# Main-PCB.net
KiCad netlist of a schematic drawn in EAGLE
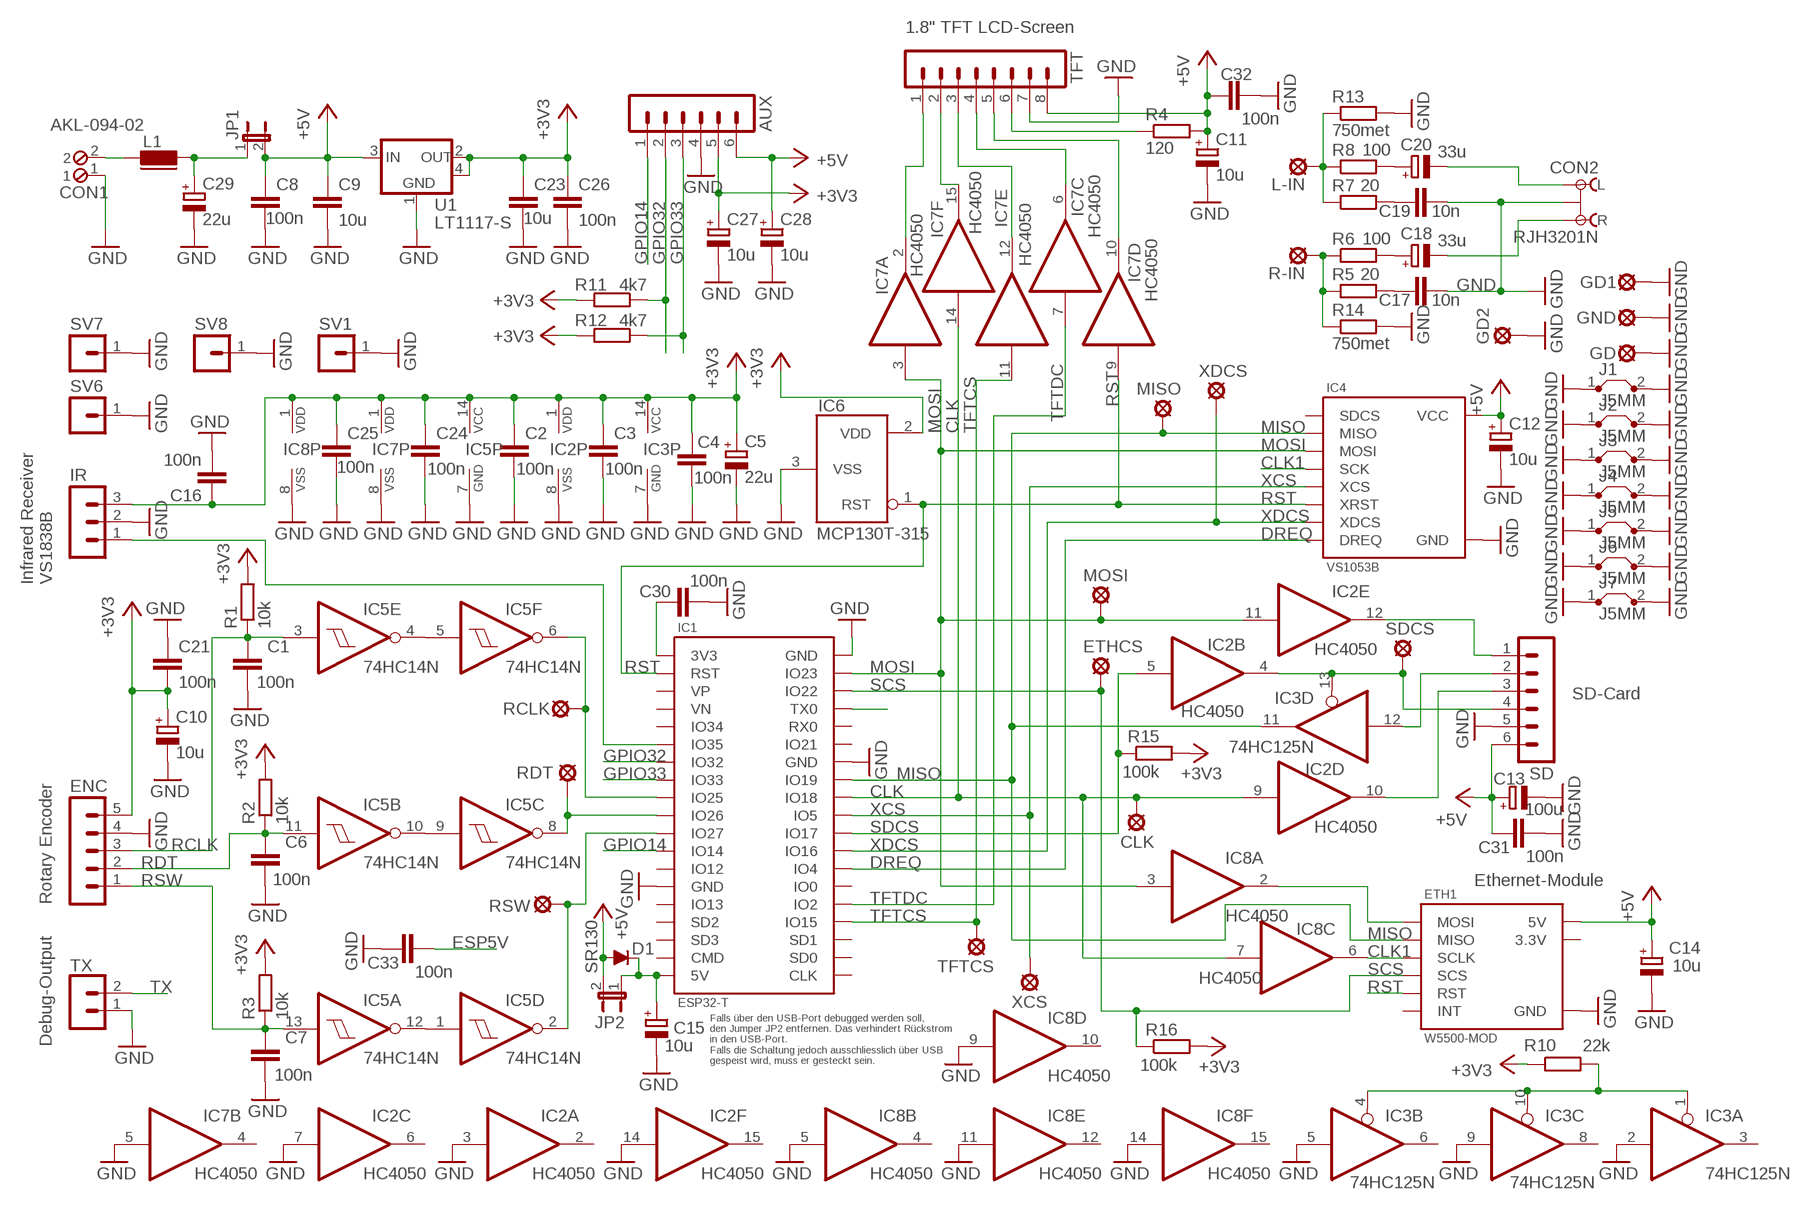
[diagram p0: schematic, sheet 1]

(export (version "E")
  (design (tool "Eeschema 10.0.6"))
  (components
    (comp (ref "AUX")
      (value "MA06-1")
      (footprint "eagle-import:MA06-1")
      (libsource (lib "eagle-import") (part "MA06-1"))
    )
    (comp (ref "C1")
      (value "100n")
      (footprint "eagle-import:C050-024X044")
      (libsource (lib "eagle-import") (part "C-EU050-024X044"))
    )
    (comp (ref "C2")
      (value "100n")
      (footprint "eagle-import:C1206")
      (libsource (lib "eagle-import") (part "C-EUC1206"))
    )
    (comp (ref "C3")
      (value "100n")
      (footprint "eagle-import:C1206")
      (libsource (lib "eagle-import") (part "C-EUC1206"))
    )
    (comp (ref "C4")
      (value "100n")
      (footprint "eagle-import:C1206")
      (libsource (lib "eagle-import") (part "C-EUC1206"))
    )
    (comp (ref "C5")
      (value "22u")
      (footprint "eagle-import:TT2D4")
      (libsource (lib "eagle-import") (part "CPOL-EUTT2D4"))
    )
    (comp (ref "C6")
      (value "100n")
      (footprint "eagle-import:C050-024X044")
      (libsource (lib "eagle-import") (part "C-EU050-024X044"))
    )
    (comp (ref "C7")
      (value "100n")
      (footprint "eagle-import:C050-024X044")
      (libsource (lib "eagle-import") (part "C-EU050-024X044"))
    )
    (comp (ref "C8")
      (value "100n")
      (footprint "eagle-import:C1206")
      (libsource (lib "eagle-import") (part "C-EUC1206"))
    )
    (comp (ref "C9")
      (value "10u")
      (footprint "eagle-import:C1206")
      (libsource (lib "eagle-import") (part "C-EUC1206"))
    )
    (comp (ref "C10")
      (value "10u")
      (footprint "eagle-import:TT2D4")
      (libsource (lib "eagle-import") (part "CPOL-EUTT2D4"))
    )
    (comp (ref "C11")
      (value "10u")
      (footprint "eagle-import:TT2D4")
      (libsource (lib "eagle-import") (part "CPOL-EUTT2D4"))
    )
    (comp (ref "C12")
      (value "10u")
      (footprint "eagle-import:TT2D4L")
      (libsource (lib "eagle-import") (part "CPOL-EUTT2D4L"))
    )
    (comp (ref "C13")
      (value "100u")
      (footprint "eagle-import:E2,5-6")
      (libsource (lib "eagle-import") (part "CPOL-EUE2.5-6"))
    )
    (comp (ref "C14")
      (value "10u")
      (footprint "eagle-import:TT2D4")
      (libsource (lib "eagle-import") (part "CPOL-EUTT2D4"))
    )
    (comp (ref "C15")
      (value "10u")
      (footprint "eagle-import:TT2D4")
      (libsource (lib "eagle-import") (part "CPOL-EUTT2D4"))
    )
    (comp (ref "C16")
      (value "100n")
      (footprint "eagle-import:C1206")
      (libsource (lib "eagle-import") (part "C-EUC1206"))
    )
    (comp (ref "C17")
      (value "10n")
      (footprint "eagle-import:C1206")
      (libsource (lib "eagle-import") (part "C-EUC1206"))
    )
    (comp (ref "C18")
      (value "33u")
      (footprint "eagle-import:TT2D4")
      (libsource (lib "eagle-import") (part "CPOL-EUTT2D4"))
    )
    (comp (ref "C19")
      (value "10n")
      (footprint "eagle-import:C1206")
      (libsource (lib "eagle-import") (part "C-EUC1206"))
    )
    (comp (ref "C20")
      (value "33u")
      (footprint "eagle-import:TT2D4")
      (libsource (lib "eagle-import") (part "CPOL-EUTT2D4"))
    )
    (comp (ref "C21")
      (value "100n")
      (footprint "eagle-import:C1206")
      (libsource (lib "eagle-import") (part "C-EUC1206"))
    )
    (comp (ref "C23")
      (value "10u")
      (footprint "eagle-import:C1206")
      (libsource (lib "eagle-import") (part "C-EUC1206"))
    )
    (comp (ref "C24")
      (value "100n")
      (footprint "eagle-import:C1206")
      (libsource (lib "eagle-import") (part "C-EUC1206"))
    )
    (comp (ref "C25")
      (value "100n")
      (footprint "eagle-import:C1206")
      (libsource (lib "eagle-import") (part "C-EUC1206"))
    )
    (comp (ref "C26")
      (value "100n")
      (footprint "eagle-import:C1206")
      (libsource (lib "eagle-import") (part "C-EUC1206"))
    )
    (comp (ref "C27")
      (value "10u")
      (footprint "eagle-import:TT2D4")
      (libsource (lib "eagle-import") (part "CPOL-EUTT2D4"))
    )
    (comp (ref "C28")
      (value "10u")
      (footprint "eagle-import:TT2D4")
      (libsource (lib "eagle-import") (part "CPOL-EUTT2D4"))
    )
    (comp (ref "C29")
      (value "22u")
      (footprint "eagle-import:TT2D4")
      (libsource (lib "eagle-import") (part "CPOL-EUTT2D4"))
    )
    (comp (ref "C30")
      (value "100n")
      (footprint "eagle-import:C1206")
      (libsource (lib "eagle-import") (part "C-EUC1206"))
    )
    (comp (ref "C31")
      (value "100n")
      (footprint "eagle-import:C1206")
      (libsource (lib "eagle-import") (part "C-EUC1206"))
    )
    (comp (ref "C32")
      (value "100n")
      (footprint "eagle-import:C1206")
      (libsource (lib "eagle-import") (part "C-EUC1206"))
    )
    (comp (ref "C33")
      (value "100n")
      (footprint "eagle-import:C1206")
      (libsource (lib "eagle-import") (part "C-EUC1206"))
    )
    (comp (ref "CLK")
      (value "LSP11")
      (footprint "eagle-import:LSP11")
      (libsource (lib "eagle-import") (part "LSP11"))
    )
    (comp (ref "CON1")
      (value "AKL-094-02")
      (footprint "eagle-import:AKL-094-02")
      (libsource (lib "eagle-import") (part "AKL-094-02"))
    )
    (comp (ref "CON2")
      (value "RJH3201N")
      (footprint "eagle-import:TECHNICS-RJH3201N")
      (libsource (lib "eagle-import") (part "RJH3201N"))
    )
    (comp (ref "D1")
      (value "SR130")
      (footprint "eagle-import:D-7.5")
      (libsource (lib "eagle-import") (part "DIODE-D-7.5"))
    )
    (comp (ref "ENC")
      (value "MA05-1")
      (footprint "eagle-import:MA05-1")
      (libsource (lib "eagle-import") (part "MA05-1"))
    )
    (comp (ref "ETH1")
      (value "W5500-MOD")
      (footprint "eagle-import:W5500-MOD")
      (libsource (lib "eagle-import") (part "W5500-MOD"))
    )
    (comp (ref "ETHCS")
      (value "LSP11")
      (footprint "eagle-import:LSP11")
      (libsource (lib "eagle-import") (part "LSP11"))
    )
    (comp (ref "GD")
      (value "LSP11")
      (footprint "eagle-import:LSP11")
      (libsource (lib "eagle-import") (part "LSP11"))
    )
    (comp (ref "GD1")
      (value "LSP11")
      (footprint "eagle-import:LSP11")
      (libsource (lib "eagle-import") (part "LSP11"))
    )
    (comp (ref "GD2")
      (value "SE13")
      (footprint "eagle-import:SE13")
      (libsource (lib "eagle-import") (part "SE13"))
    )
    (comp (ref "GND")
      (value "LSP11")
      (footprint "eagle-import:LSP11")
      (libsource (lib "eagle-import") (part "LSP11"))
    )
    (comp (ref "IC1")
      (value "ESP32-T")
      (footprint "eagle-import:ESP32-T")
      (libsource (lib "eagle-import") (part "ESP32-T"))
    )
    (comp (ref "IC2")
      (value "HC4050")
      (footprint "eagle-import:DIL16")
      (libsource (lib "eagle-import") (part "4050N"))
    )
    (comp (ref "IC3")
      (value "74HC125N")
      (footprint "eagle-import:DIL14")
      (libsource (lib "eagle-import") (part "74125NHC"))
    )
    (comp (ref "IC4")
      (value "VS1053B")
      (footprint "eagle-import:VS1053B")
      (libsource (lib "eagle-import") (part "VS1053B"))
    )
    (comp (ref "IC5")
      (value "74HC14N")
      (footprint "eagle-import:DIL14")
      (libsource (lib "eagle-import") (part "7414NHC"))
    )
    (comp (ref "IC6")
      (value "MCP130T-315")
      (footprint "eagle-import:SOT-23")
      (libsource (lib "eagle-import") (part "MCP130T-XXXSOT-23"))
    )
    (comp (ref "IC7")
      (value "HC4050")
      (footprint "eagle-import:DIL16")
      (libsource (lib "eagle-import") (part "4050N"))
    )
    (comp (ref "IC8")
      (value "HC4050")
      (footprint "eagle-import:DIL16")
      (libsource (lib "eagle-import") (part "4050N"))
    )
    (comp (ref "IR")
      (value "MA03-1")
      (footprint "eagle-import:MA03-1")
      (libsource (lib "eagle-import") (part "MA03-1"))
    )
    (comp (ref "J1")
      (value "J5MM")
      (footprint "eagle-import:05")
      (libsource (lib "eagle-import") (part "J5MM"))
    )
    (comp (ref "J2")
      (value "J5MM")
      (footprint "eagle-import:05")
      (libsource (lib "eagle-import") (part "J5MM"))
    )
    (comp (ref "J3")
      (value "J5MM")
      (footprint "eagle-import:05")
      (libsource (lib "eagle-import") (part "J5MM"))
    )
    (comp (ref "J4")
      (value "J5MM")
      (footprint "eagle-import:05")
      (libsource (lib "eagle-import") (part "J5MM"))
    )
    (comp (ref "J5")
      (value "J5MM")
      (footprint "eagle-import:05")
      (libsource (lib "eagle-import") (part "J5MM"))
    )
    (comp (ref "J6")
      (value "J5MM")
      (footprint "eagle-import:05")
      (libsource (lib "eagle-import") (part "J5MM"))
    )
    (comp (ref "J7")
      (value "J5MM")
      (footprint "eagle-import:05")
      (libsource (lib "eagle-import") (part "J5MM"))
    )
    (comp (ref "JP1")
      (value "JP1E")
      (footprint "eagle-import:JP1")
      (libsource (lib "eagle-import") (part "JP1E"))
    )
    (comp (ref "JP2")
      (value "JP1E")
      (footprint "eagle-import:JP1")
      (libsource (lib "eagle-import") (part "JP1E"))
    )
    (comp (ref "L-IN")
      (value "LSP11")
      (footprint "eagle-import:LSP11")
      (libsource (lib "eagle-import") (part "LSP11"))
    )
    (comp (ref "L1")
      (value "07HCP")
      (footprint "eagle-import:07HCP")
      (libsource (lib "eagle-import") (part "07HCP"))
    )
    (comp (ref "MISO")
      (value "LSP11")
      (footprint "eagle-import:LSP11")
      (libsource (lib "eagle-import") (part "LSP11"))
    )
    (comp (ref "MOSI")
      (value "LSP11")
      (footprint "eagle-import:LSP11")
      (libsource (lib "eagle-import") (part "LSP11"))
    )
    (comp (ref "R-IN")
      (value "LSP11")
      (footprint "eagle-import:LSP11")
      (libsource (lib "eagle-import") (part "LSP11"))
    )
    (comp (ref "R1")
      (value "10k")
      (footprint "eagle-import:0207_10")
      (libsource (lib "eagle-import") (part "R-EU_0207/10"))
    )
    (comp (ref "R2")
      (value "10k")
      (footprint "eagle-import:0207_10")
      (libsource (lib "eagle-import") (part "R-EU_0207/10"))
    )
    (comp (ref "R3")
      (value "10k")
      (footprint "eagle-import:0207_10")
      (libsource (lib "eagle-import") (part "R-EU_0207/10"))
    )
    (comp (ref "R4")
      (value "120")
      (footprint "eagle-import:0207_10")
      (libsource (lib "eagle-import") (part "R-EU_0207/10"))
    )
    (comp (ref "R5")
      (value "20")
      (footprint "eagle-import:R1206")
      (libsource (lib "eagle-import") (part "R-EU_R1206"))
    )
    (comp (ref "R6")
      (value "100")
      (footprint "eagle-import:R1206")
      (libsource (lib "eagle-import") (part "R-EU_R1206"))
    )
    (comp (ref "R7")
      (value "20")
      (footprint "eagle-import:R1206")
      (libsource (lib "eagle-import") (part "R-EU_R1206"))
    )
    (comp (ref "R8")
      (value "100")
      (footprint "eagle-import:R1206")
      (libsource (lib "eagle-import") (part "R-EU_R1206"))
    )
    (comp (ref "R10")
      (value "22k")
      (footprint "eagle-import:R1206")
      (libsource (lib "eagle-import") (part "R-EU_R1206"))
    )
    (comp (ref "R11")
      (value "4k7")
      (footprint "eagle-import:R1206")
      (libsource (lib "eagle-import") (part "R-EU_R1206"))
    )
    (comp (ref "R12")
      (value "4k7")
      (footprint "eagle-import:R1206")
      (libsource (lib "eagle-import") (part "R-EU_R1206"))
    )
    (comp (ref "R13")
      (value "750met")
      (footprint "eagle-import:0207_10")
      (libsource (lib "eagle-import") (part "R-EU_0207/10"))
    )
    (comp (ref "R14")
      (value "750met")
      (footprint "eagle-import:0207_10")
      (libsource (lib "eagle-import") (part "R-EU_0207/10"))
    )
    (comp (ref "R15")
      (value "100k")
      (footprint "eagle-import:R1206")
      (libsource (lib "eagle-import") (part "R-EU_R1206"))
    )
    (comp (ref "R16")
      (value "100k")
      (footprint "eagle-import:R1206")
      (libsource (lib "eagle-import") (part "R-EU_R1206"))
    )
    (comp (ref "RCLK")
      (value "LSP11")
      (footprint "eagle-import:LSP11")
      (libsource (lib "eagle-import") (part "LSP11"))
    )
    (comp (ref "RDT")
      (value "LSP11")
      (footprint "eagle-import:LSP11")
      (libsource (lib "eagle-import") (part "LSP11"))
    )
    (comp (ref "RSW")
      (value "LSP11")
      (footprint "eagle-import:LSP11")
      (libsource (lib "eagle-import") (part "LSP11"))
    )
    (comp (ref "SD")
      (value "MA06-1")
      (footprint "eagle-import:MA06-1")
      (libsource (lib "eagle-import") (part "MA06-1"))
    )
    (comp (ref "SDCS")
      (value "LSP11")
      (footprint "eagle-import:LSP11")
      (libsource (lib "eagle-import") (part "LSP11"))
    )
    (comp (ref "SV1")
      (value "MA01-1")
      (footprint "eagle-import:MA01-1")
      (libsource (lib "eagle-import") (part "MA01-1"))
    )
    (comp (ref "SV6")
      (value "MA01-1")
      (footprint "eagle-import:MA01-1")
      (libsource (lib "eagle-import") (part "MA01-1"))
    )
    (comp (ref "SV7")
      (value "MA01-1")
      (footprint "eagle-import:MA01-1")
      (libsource (lib "eagle-import") (part "MA01-1"))
    )
    (comp (ref "SV8")
      (value "MA01-1")
      (footprint "eagle-import:MA01-1")
      (libsource (lib "eagle-import") (part "MA01-1"))
    )
    (comp (ref "TFT")
      (value "MA08-1")
      (footprint "eagle-import:MA08-1")
      (libsource (lib "eagle-import") (part "MA08-1"))
    )
    (comp (ref "TFTCS")
      (value "LSP11")
      (footprint "eagle-import:LSP11")
      (libsource (lib "eagle-import") (part "LSP11"))
    )
    (comp (ref "TX")
      (value "MA02-1")
      (footprint "eagle-import:MA02-1")
      (libsource (lib "eagle-import") (part "MA02-1"))
    )
    (comp (ref "U1")
      (value "LT1117-S")
      (footprint "eagle-import:SOT223")
      (libsource (lib "eagle-import") (part "LT1117-S"))
    )
    (comp (ref "XCS")
      (value "LSP11")
      (footprint "eagle-import:LSP11")
      (libsource (lib "eagle-import") (part "LSP11"))
    )
    (comp (ref "XDCS")
      (value "LSP11")
      (footprint "eagle-import:LSP11")
      (libsource (lib "eagle-import") (part "LSP11"))
    )
  )
  (nets
    (net (code "1") (name "+3V3") (class "Default")
      (node (ref "AUX") (pin "5") (pinfunction "5_5") (pintype "passive"))
      (node (ref "C10") (pin "+") (pinfunction "+_+") (pintype "passive"))
      (node (ref "C16") (pin "1") (pinfunction "1_1") (pintype "passive"))
      (node (ref "C2") (pin "1") (pinfunction "1_1") (pintype "passive"))
      (node (ref "C21") (pin "2") (pinfunction "2_2") (pintype "passive"))
      (node (ref "C23") (pin "1") (pinfunction "1_1") (pintype "passive"))
      (node (ref "C24") (pin "1") (pinfunction "1_1") (pintype "passive"))
      (node (ref "C25") (pin "1") (pinfunction "1_1") (pintype "passive"))
      (node (ref "C26") (pin "1") (pinfunction "1_1") (pintype "passive"))
      (node (ref "C27") (pin "+") (pinfunction "+_+") (pintype "passive"))
      (node (ref "C3") (pin "1") (pinfunction "1_1") (pintype "passive"))
      (node (ref "C4") (pin "1") (pinfunction "1_1") (pintype "passive"))
      (node (ref "C5") (pin "+") (pinfunction "+_+") (pintype "passive"))
      (node (ref "ENC") (pin "5") (pinfunction "5_5") (pintype "passive"))
      (node (ref "IC2") (pin "1") (pinfunction "VDD_1") (pintype "power_in"))
      (node (ref "IC3") (pin "14") (pinfunction "VCC_14") (pintype "power_in"))
      (node (ref "IC5") (pin "14") (pinfunction "VCC_14") (pintype "power_in"))
      (node (ref "IC6") (pin "2") (pinfunction "VDD_2") (pintype "power_in"))
      (node (ref "IC7") (pin "1") (pinfunction "VDD_1") (pintype "power_in"))
      (node (ref "IC8") (pin "1") (pinfunction "VDD_1") (pintype "power_in"))
      (node (ref "IR") (pin "3") (pinfunction "3_3") (pintype "passive"))
      (node (ref "R1") (pin "2") (pinfunction "2_2") (pintype "passive"))
      (node (ref "R10") (pin "1") (pinfunction "1_1") (pintype "passive"))
      (node (ref "R11") (pin "2") (pinfunction "2_2") (pintype "passive"))
      (node (ref "R12") (pin "2") (pinfunction "2_2") (pintype "passive"))
      (node (ref "R15") (pin "2") (pinfunction "2_2") (pintype "passive"))
      (node (ref "R16") (pin "2") (pinfunction "2_2") (pintype "passive"))
      (node (ref "R2") (pin "2") (pinfunction "2_2") (pintype "passive"))
      (node (ref "R3") (pin "2") (pinfunction "2_2") (pintype "passive"))
      (node (ref "U1") (pin "2") (pinfunction "OUT_2") (pintype "passive"))
      (node (ref "U1") (pin "4") (pinfunction "TAB_4") (pintype "passive"))
    )
    (net (code "2") (name "+5V") (class "Default")
      (node (ref "AUX") (pin "6") (pinfunction "6_6") (pintype "passive"))
      (node (ref "C11") (pin "+") (pinfunction "+_+") (pintype "passive"))
      (node (ref "C12") (pin "+") (pinfunction "+_+") (pintype "passive"))
      (node (ref "C13") (pin "+") (pinfunction "+_+") (pintype "passive"))
      (node (ref "C14") (pin "+") (pinfunction "+_+") (pintype "passive"))
      (node (ref "C28") (pin "+") (pinfunction "+_+") (pintype "passive"))
      (node (ref "C31") (pin "2") (pinfunction "2_2") (pintype "passive"))
      (node (ref "C32") (pin "2") (pinfunction "2_2") (pintype "passive"))
      (node (ref "C8") (pin "1") (pinfunction "1_1") (pintype "passive"))
      (node (ref "C9") (pin "1") (pinfunction "1_1") (pintype "passive"))
      (node (ref "D1") (pin "A") (pinfunction "A_A") (pintype "passive"))
      (node (ref "ETH1") (pin "5V") (pinfunction "5V_5V") (pintype "power_in"))
      (node (ref "IC4") (pin "5V") (pinfunction "VCC_5V") (pintype "power_in"))
      (node (ref "JP1") (pin "2") (pinfunction "2_2") (pintype "passive"))
      (node (ref "JP2") (pin "2") (pinfunction "2_2") (pintype "passive"))
      (node (ref "R4") (pin "2") (pinfunction "2_2") (pintype "passive"))
      (node (ref "SD") (pin "6") (pinfunction "6_6") (pintype "passive"))
      (node (ref "TFT") (pin "8") (pinfunction "8_8") (pintype "passive"))
      (node (ref "U1") (pin "3") (pinfunction "IN_3") (pintype "input"))
    )
    (net (code "3") (name "/3.3V") (class "Default")
      (node (ref "ETH1") (pin "3.3V") (pinfunction "3.3V_3.3V") (pintype "power_in"))
    )
    (net (code "4") (name "/CLK") (class "Default")
      (node (ref "CLK") (pin "MP") (pinfunction "MP_MP") (pintype "passive"))
      (node (ref "IC1") (pin "IO18") (pinfunction "IO18_IO18") (pintype "bidirectional"))
      (node (ref "IC2") (pin "9") (pinfunction "I_9") (pintype "input"))
      (node (ref "IC7") (pin "14") (pinfunction "I_14") (pintype "input"))
      (node (ref "IC8") (pin "7") (pinfunction "I_7") (pintype "input"))
    )
    (net (code "5") (name "/CLK1") (class "Default")
      (node (ref "ETH1") (pin "SCLK") (pinfunction "SCLK_SCLK") (pintype "input"))
      (node (ref "IC4") (pin "SCK") (pinfunction "SCK_SCK") (pintype "input"))
      (node (ref "IC8") (pin "6") (pinfunction "O_6") (pintype "output"))
    )
    (net (code "6") (name "/DREQ") (class "Default")
      (node (ref "IC1") (pin "IO4") (pinfunction "IO4_IO4") (pintype "bidirectional"))
      (node (ref "IC4") (pin "DREQ") (pinfunction "DREQ_DREQ") (pintype "output"))
    )
    (net (code "7") (name "/ESP5V") (class "Default")
      (node (ref "C15") (pin "+") (pinfunction "+_+") (pintype "passive"))
      (node (ref "C33") (pin "1") (pinfunction "1_1") (pintype "passive"))
      (node (ref "D1") (pin "C") (pinfunction "C_C") (pintype "passive"))
      (node (ref "IC1") (pin "5V") (pinfunction "5V_5V") (pintype "power_in"))
      (node (ref "JP2") (pin "1") (pinfunction "1_1") (pintype "passive"))
    )
    (net (code "8") (name "/GPIO14") (class "Default")
      (node (ref "AUX") (pin "1") (pinfunction "1_1") (pintype "passive"))
      (node (ref "IC1") (pin "IO14") (pinfunction "IO14_IO14") (pintype "bidirectional"))
    )
    (net (code "9") (name "/GPIO32") (class "Default")
      (node (ref "AUX") (pin "2") (pinfunction "2_2") (pintype "passive"))
      (node (ref "IC1") (pin "IO32") (pinfunction "IO32_IO32") (pintype "bidirectional"))
      (node (ref "R11") (pin "1") (pinfunction "1_1") (pintype "passive"))
    )
    (net (code "10") (name "/GPIO33") (class "Default")
      (node (ref "AUX") (pin "3") (pinfunction "3_3") (pintype "passive"))
      (node (ref "IC1") (pin "IO33") (pinfunction "IO33_IO33") (pintype "bidirectional"))
      (node (ref "R12") (pin "1") (pinfunction "1_1") (pintype "passive"))
    )
    (net (code "11") (name "/MISO") (class "Default")
      (node (ref "ETH1") (pin "MISO") (pinfunction "MISO_MISO") (pintype "output"))
      (node (ref "IC1") (pin "IO19") (pinfunction "IO19_IO19") (pintype "bidirectional"))
      (node (ref "IC3") (pin "11") (pinfunction "O_11") (pintype "tri_state"))
      (node (ref "IC4") (pin "MISO") (pinfunction "MISO_MISO") (pintype "output"))
      (node (ref "MISO") (pin "MP") (pinfunction "MP_MP") (pintype "passive"))
    )
    (net (code "12") (name "/MOSI") (class "Default")
      (node (ref "IC1") (pin "IO23") (pinfunction "IO23_IO23") (pintype "bidirectional"))
      (node (ref "IC2") (pin "11") (pinfunction "I_11") (pintype "input"))
      (node (ref "IC4") (pin "MOSI") (pinfunction "MOSI_MOSI") (pintype "input"))
      (node (ref "IC7") (pin "3") (pinfunction "I_3") (pintype "input"))
      (node (ref "IC8") (pin "3") (pinfunction "I_3") (pintype "input"))
      (node (ref "MOSI") (pin "MP") (pinfunction "MP_MP") (pintype "passive"))
    )
    (net (code "13") (name "/RCLK") (class "Default")
      (node (ref "C1") (pin "1") (pinfunction "1_1") (pintype "passive"))
      (node (ref "ENC") (pin "3") (pinfunction "3_3") (pintype "passive"))
      (node (ref "IC5") (pin "3") (pinfunction "I_3") (pintype "input"))
      (node (ref "R1") (pin "1") (pinfunction "1_1") (pintype "passive"))
    )
    (net (code "14") (name "/RDT") (class "Default")
      (node (ref "C6") (pin "1") (pinfunction "1_1") (pintype "passive"))
      (node (ref "ENC") (pin "2") (pinfunction "2_2") (pintype "passive"))
      (node (ref "IC5") (pin "11") (pinfunction "I_11") (pintype "input"))
      (node (ref "R2") (pin "1") (pinfunction "1_1") (pintype "passive"))
    )
    (net (code "15") (name "/RST") (class "Default")
      (node (ref "ETH1") (pin "RST") (pinfunction "RST_RST") (pintype "input"))
      (node (ref "IC1") (pin "RST") (pinfunction "RST_RST") (pintype "bidirectional"))
      (node (ref "IC4") (pin "XRST") (pinfunction "XRST_XRST") (pintype "input"))
      (node (ref "IC6") (pin "1") (pinfunction "RST_1") (pintype "output"))
      (node (ref "IC7") (pin "9") (pinfunction "I_9") (pintype "input"))
    )
    (net (code "16") (name "/RSW") (class "Default")
      (node (ref "C7") (pin "1") (pinfunction "1_1") (pintype "passive"))
      (node (ref "ENC") (pin "1") (pinfunction "1_1") (pintype "passive"))
      (node (ref "IC5") (pin "13") (pinfunction "I_13") (pintype "input"))
      (node (ref "R3") (pin "1") (pinfunction "1_1") (pintype "passive"))
    )
    (net (code "17") (name "/SCS") (class "Default")
      (node (ref "ETH1") (pin "SCS") (pinfunction "SCS_SCS") (pintype "input"))
      (node (ref "ETHCS") (pin "MP") (pinfunction "MP_MP") (pintype "passive"))
      (node (ref "IC1") (pin "IO22") (pinfunction "IO22_IO22") (pintype "bidirectional"))
      (node (ref "R16") (pin "1") (pinfunction "1_1") (pintype "passive"))
    )
    (net (code "18") (name "/SDCS") (class "Default")
      (node (ref "IC1") (pin "IO17") (pinfunction "IO17_IO17") (pintype "bidirectional"))
      (node (ref "IC2") (pin "5") (pinfunction "I_5") (pintype "input"))
      (node (ref "R15") (pin "1") (pinfunction "1_1") (pintype "passive"))
    )
    (net (code "19") (name "/TFTCS") (class "Default")
      (node (ref "IC1") (pin "IO15") (pinfunction "IO15_IO15") (pintype "bidirectional"))
      (node (ref "IC7") (pin "11") (pinfunction "I_11") (pintype "input"))
      (node (ref "TFTCS") (pin "MP") (pinfunction "MP_MP") (pintype "passive"))
    )
    (net (code "20") (name "/TFTDC") (class "Default")
      (node (ref "IC1") (pin "IO2") (pinfunction "IO2_IO2") (pintype "bidirectional"))
      (node (ref "IC7") (pin "7") (pinfunction "I_7") (pintype "input"))
    )
    (net (code "21") (name "/TX") (class "Default")
      (node (ref "IC1") (pin "TX0") (pinfunction "TX0_TX0") (pintype "output"))
      (node (ref "TX") (pin "2") (pinfunction "2_2") (pintype "passive"))
    )
    (net (code "22") (name "/XCS") (class "Default")
      (node (ref "IC1") (pin "IO5") (pinfunction "IO5_IO5") (pintype "bidirectional"))
      (node (ref "IC4") (pin "XCS") (pinfunction "XCS_XCS") (pintype "input"))
      (node (ref "XCS") (pin "MP") (pinfunction "MP_MP") (pintype "passive"))
    )
    (net (code "23") (name "/XDCS") (class "Default")
      (node (ref "IC1") (pin "IO16") (pinfunction "IO16_IO16") (pintype "bidirectional"))
      (node (ref "IC4") (pin "XDCS") (pinfunction "XDCS_XDCS") (pintype "input"))
      (node (ref "XDCS") (pin "MP") (pinfunction "MP_MP") (pintype "passive"))
    )
    (net (code "24") (name "GND") (class "Default")
      (node (ref "AUX") (pin "4") (pinfunction "4_4") (pintype "passive"))
      (node (ref "C1") (pin "2") (pinfunction "2_2") (pintype "passive"))
      (node (ref "C10") (pin "-") (pinfunction "-_-") (pintype "passive"))
      (node (ref "C11") (pin "-") (pinfunction "-_-") (pintype "passive"))
      (node (ref "C12") (pin "-") (pinfunction "-_-") (pintype "passive"))
      (node (ref "C13") (pin "-") (pinfunction "-_-") (pintype "passive"))
      (node (ref "C14") (pin "-") (pinfunction "-_-") (pintype "passive"))
      (node (ref "C15") (pin "-") (pinfunction "-_-") (pintype "passive"))
      (node (ref "C16") (pin "2") (pinfunction "2_2") (pintype "passive"))
      (node (ref "C17") (pin "2") (pinfunction "2_2") (pintype "passive"))
      (node (ref "C19") (pin "2") (pinfunction "2_2") (pintype "passive"))
      (node (ref "C2") (pin "2") (pinfunction "2_2") (pintype "passive"))
      (node (ref "C21") (pin "1") (pinfunction "1_1") (pintype "passive"))
      (node (ref "C23") (pin "2") (pinfunction "2_2") (pintype "passive"))
      (node (ref "C24") (pin "2") (pinfunction "2_2") (pintype "passive"))
      (node (ref "C25") (pin "2") (pinfunction "2_2") (pintype "passive"))
      (node (ref "C26") (pin "2") (pinfunction "2_2") (pintype "passive"))
      (node (ref "C27") (pin "-") (pinfunction "-_-") (pintype "passive"))
      (node (ref "C28") (pin "-") (pinfunction "-_-") (pintype "passive"))
      (node (ref "C29") (pin "-") (pinfunction "-_-") (pintype "passive"))
      (node (ref "C3") (pin "2") (pinfunction "2_2") (pintype "passive"))
      (node (ref "C30") (pin "2") (pinfunction "2_2") (pintype "passive"))
      (node (ref "C31") (pin "1") (pinfunction "1_1") (pintype "passive"))
      (node (ref "C32") (pin "1") (pinfunction "1_1") (pintype "passive"))
      (node (ref "C33") (pin "2") (pinfunction "2_2") (pintype "passive"))
      (node (ref "C4") (pin "2") (pinfunction "2_2") (pintype "passive"))
      (node (ref "C5") (pin "-") (pinfunction "-_-") (pintype "passive"))
      (node (ref "C6") (pin "2") (pinfunction "2_2") (pintype "passive"))
      (node (ref "C7") (pin "2") (pinfunction "2_2") (pintype "passive"))
      (node (ref "C8") (pin "2") (pinfunction "2_2") (pintype "passive"))
      (node (ref "C9") (pin "2") (pinfunction "2_2") (pintype "passive"))
      (node (ref "CON1") (pin "1") (pinfunction "1_1") (pintype "passive"))
      (node (ref "CON2") (pin "GND") (pinfunction "GND_GND") (pintype "passive"))
      (node (ref "ENC") (pin "4") (pinfunction "4_4") (pintype "passive"))
      (node (ref "ETH1") (pin "GND") (pinfunction "GND_GND") (pintype "power_in"))
      (node (ref "GD") (pin "MP") (pinfunction "MP_MP") (pintype "passive"))
      (node (ref "GD1") (pin "MP") (pinfunction "MP_MP") (pintype "passive"))
      (node (ref "GD2") (pin "MP") (pinfunction "MP_MP") (pintype "passive"))
      (node (ref "GND") (pin "MP") (pinfunction "MP_MP") (pintype "passive"))
      (node (ref "IC1") (pin "GND") (pinfunction "GND_GND") (pintype "power_in"))
      (node (ref "IC1") (pin "GND1") (pinfunction "GND_GND1") (pintype "power_in"))
      (node (ref "IC1") (pin "GND2") (pinfunction "GND_GND2") (pintype "power_in"))
      (node (ref "IC2") (pin "14") (pinfunction "I_14") (pintype "input"))
      (node (ref "IC2") (pin "3") (pinfunction "I_3") (pintype "input"))
      (node (ref "IC2") (pin "7") (pinfunction "I_7") (pintype "input"))
      (node (ref "IC2") (pin "8") (pinfunction "VSS_8") (pintype "power_in"))
      (node (ref "IC3") (pin "2") (pinfunction "I_2") (pintype "input"))
      (node (ref "IC3") (pin "5") (pinfunction "I_5") (pintype "input"))
      (node (ref "IC3") (pin "7") (pinfunction "GND_7") (pintype "power_in"))
      (node (ref "IC3") (pin "9") (pinfunction "I_9") (pintype "input"))
      (node (ref "IC4") (pin "GND") (pinfunction "GND_GND") (pintype "power_in"))
      (node (ref "IC5") (pin "7") (pinfunction "GND_7") (pintype "power_in"))
      (node (ref "IC6") (pin "3") (pinfunction "VSS_3") (pintype "power_in"))
      (node (ref "IC7") (pin "5") (pinfunction "I_5") (pintype "input"))
      (node (ref "IC7") (pin "8") (pinfunction "VSS_8") (pintype "power_in"))
      (node (ref "IC8") (pin "11") (pinfunction "I_11") (pintype "input"))
      (node (ref "IC8") (pin "14") (pinfunction "I_14") (pintype "input"))
      (node (ref "IC8") (pin "5") (pinfunction "I_5") (pintype "input"))
      (node (ref "IC8") (pin "8") (pinfunction "VSS_8") (pintype "power_in"))
      (node (ref "IC8") (pin "9") (pinfunction "I_9") (pintype "input"))
      (node (ref "IR") (pin "2") (pinfunction "2_2") (pintype "passive"))
      (node (ref "J1") (pin "1") (pinfunction "1_1") (pintype "passive"))
      (node (ref "J1") (pin "2") (pinfunction "2_2") (pintype "passive"))
      (node (ref "J2") (pin "1") (pinfunction "1_1") (pintype "passive"))
      (node (ref "J2") (pin "2") (pinfunction "2_2") (pintype "passive"))
      (node (ref "J3") (pin "1") (pinfunction "1_1") (pintype "passive"))
      (node (ref "J3") (pin "2") (pinfunction "2_2") (pintype "passive"))
      (node (ref "J4") (pin "1") (pinfunction "1_1") (pintype "passive"))
      (node (ref "J4") (pin "2") (pinfunction "2_2") (pintype "passive"))
      (node (ref "J5") (pin "1") (pinfunction "1_1") (pintype "passive"))
      (node (ref "J5") (pin "2") (pinfunction "2_2") (pintype "passive"))
      (node (ref "J6") (pin "1") (pinfunction "1_1") (pintype "passive"))
      (node (ref "J6") (pin "2") (pinfunction "2_2") (pintype "passive"))
      (node (ref "J7") (pin "1") (pinfunction "1_1") (pintype "passive"))
      (node (ref "J7") (pin "2") (pinfunction "2_2") (pintype "passive"))
      (node (ref "R13") (pin "2") (pinfunction "2_2") (pintype "passive"))
      (node (ref "R14") (pin "2") (pinfunction "2_2") (pintype "passive"))
      (node (ref "SD") (pin "5") (pinfunction "5_5") (pintype "passive"))
      (node (ref "SV1") (pin "1") (pinfunction "1_1") (pintype "passive"))
      (node (ref "SV6") (pin "1") (pinfunction "1_1") (pintype "passive"))
      (node (ref "SV7") (pin "1") (pinfunction "1_1") (pintype "passive"))
      (node (ref "SV8") (pin "1") (pinfunction "1_1") (pintype "passive"))
      (node (ref "TFT") (pin "7") (pinfunction "7_7") (pintype "passive"))
      (node (ref "TX") (pin "1") (pinfunction "1_1") (pintype "passive"))
      (node (ref "U1") (pin "1") (pinfunction "GND_1") (pintype "input"))
    )
    (net (code "25") (name "Net-(C17-Pad1)") (class "Default")
      (node (ref "C17") (pin "1") (pinfunction "1_1") (pintype "passive"))
      (node (ref "R5") (pin "2") (pinfunction "2_2") (pintype "passive"))
    )
    (net (code "26") (name "Net-(C18-Pad+)") (class "Default")
      (node (ref "C18") (pin "+") (pinfunction "+_+") (pintype "passive"))
      (node (ref "R6") (pin "2") (pinfunction "2_2") (pintype "passive"))
    )
    (net (code "27") (name "Net-(C18-Pad-)") (class "Default")
      (node (ref "C18") (pin "-") (pinfunction "-_-") (pintype "passive"))
      (node (ref "CON2") (pin "R") (pinfunction "R_R") (pintype "passive"))
    )
    (net (code "28") (name "Net-(C19-Pad1)") (class "Default")
      (node (ref "C19") (pin "1") (pinfunction "1_1") (pintype "passive"))
      (node (ref "R7") (pin "2") (pinfunction "2_2") (pintype "passive"))
    )
    (net (code "29") (name "Net-(C20-Pad+)") (class "Default")
      (node (ref "C20") (pin "+") (pinfunction "+_+") (pintype "passive"))
      (node (ref "R8") (pin "2") (pinfunction "2_2") (pintype "passive"))
    )
    (net (code "30") (name "Net-(C20-Pad-)") (class "Default")
      (node (ref "C20") (pin "-") (pinfunction "-_-") (pintype "passive"))
      (node (ref "CON2") (pin "L") (pinfunction "L_L") (pintype "passive"))
    )
    (net (code "31") (name "Net-(C29-Pad+)") (class "Default")
      (node (ref "C29") (pin "+") (pinfunction "+_+") (pintype "passive"))
      (node (ref "JP1") (pin "1") (pinfunction "1_1") (pintype "passive"))
      (node (ref "L1") (pin "2") (pinfunction "2_2") (pintype "passive"))
    )
    (net (code "32") (name "Net-(C30-Pad1)") (class "Default")
      (node (ref "C30") (pin "1") (pinfunction "1_1") (pintype "passive"))
      (node (ref "IC1") (pin "3V3") (pinfunction "3V3_3V3") (pintype "power_in"))
    )
    (net (code "33") (name "Net-(CON1-Pad2)") (class "Default")
      (node (ref "CON1") (pin "2") (pinfunction "2_2") (pintype "passive"))
      (node (ref "L1") (pin "1") (pinfunction "1_1") (pintype "passive"))
    )
    (net (code "34") (name "Net-(IC1-PadIO35)") (class "Default")
      (node (ref "IC1") (pin "IO35") (pinfunction "IO35_IO35") (pintype "bidirectional"))
      (node (ref "IR") (pin "1") (pinfunction "1_1") (pintype "passive"))
    )
    (net (code "35") (name "Net-(IC2B-O)") (class "Default")
      (node (ref "IC2") (pin "4") (pinfunction "O_4") (pintype "output"))
      (node (ref "IC3") (pin "13") (pinfunction "OE_13") (pintype "input"))
      (node (ref "SD") (pin "4") (pinfunction "4_4") (pintype "passive"))
      (node (ref "SDCS") (pin "MP") (pinfunction "MP_MP") (pintype "passive"))
    )
    (net (code "36") (name "Net-(IC2D-O)") (class "Default")
      (node (ref "IC2") (pin "10") (pinfunction "O_10") (pintype "output"))
      (node (ref "SD") (pin "3") (pinfunction "3_3") (pintype "passive"))
    )
    (net (code "37") (name "Net-(IC2E-O)") (class "Default")
      (node (ref "IC2") (pin "12") (pinfunction "O_12") (pintype "output"))
      (node (ref "SD") (pin "1") (pinfunction "1_1") (pintype "passive"))
    )
    (net (code "38") (name "Net-(IC3A-OE)") (class "Default")
      (node (ref "IC3") (pin "1") (pinfunction "OE_1") (pintype "input"))
      (node (ref "IC3") (pin "10") (pinfunction "OE_10") (pintype "input"))
      (node (ref "IC3") (pin "4") (pinfunction "OE_4") (pintype "input"))
      (node (ref "R10") (pin "2") (pinfunction "2_2") (pintype "passive"))
    )
    (net (code "39") (name "Net-(IC3D-I)") (class "Default")
      (node (ref "IC3") (pin "12") (pinfunction "I_12") (pintype "input"))
      (node (ref "SD") (pin "2") (pinfunction "2_2") (pintype "passive"))
    )
    (net (code "40") (name "Net-(IC5A-O)") (class "Default")
      (node (ref "IC5") (pin "1") (pinfunction "I_1") (pintype "input"))
      (node (ref "IC5") (pin "12") (pinfunction "O_12") (pintype "output"))
    )
    (net (code "41") (name "Net-(IC5B-O)") (class "Default")
      (node (ref "IC5") (pin "10") (pinfunction "O_10") (pintype "output"))
      (node (ref "IC5") (pin "9") (pinfunction "I_9") (pintype "input"))
    )
    (net (code "42") (name "Net-(IC5C-O)") (class "Default")
      (node (ref "IC1") (pin "IO26") (pinfunction "IO26_IO26") (pintype "bidirectional"))
      (node (ref "IC5") (pin "8") (pinfunction "O_8") (pintype "output"))
      (node (ref "RDT") (pin "MP") (pinfunction "MP_MP") (pintype "passive"))
    )
    (net (code "43") (name "Net-(IC5D-O)") (class "Default")
      (node (ref "IC1") (pin "IO27") (pinfunction "IO27_IO27") (pintype "bidirectional"))
      (node (ref "IC5") (pin "2") (pinfunction "O_2") (pintype "output"))
      (node (ref "RSW") (pin "MP") (pinfunction "MP_MP") (pintype "passive"))
    )
    (net (code "44") (name "Net-(IC5E-O)") (class "Default")
      (node (ref "IC5") (pin "4") (pinfunction "O_4") (pintype "output"))
      (node (ref "IC5") (pin "5") (pinfunction "I_5") (pintype "input"))
    )
    (net (code "45") (name "Net-(IC5F-O)") (class "Default")
      (node (ref "IC1") (pin "IO25") (pinfunction "IO25_IO25") (pintype "bidirectional"))
      (node (ref "IC5") (pin "6") (pinfunction "O_6") (pintype "output"))
      (node (ref "RCLK") (pin "MP") (pinfunction "MP_MP") (pintype "passive"))
    )
    (net (code "46") (name "Net-(IC7A-O)") (class "Default")
      (node (ref "IC7") (pin "2") (pinfunction "O_2") (pintype "output"))
      (node (ref "TFT") (pin "1") (pinfunction "1_1") (pintype "passive"))
    )
    (net (code "47") (name "Net-(IC7C-O)") (class "Default")
      (node (ref "IC7") (pin "6") (pinfunction "O_6") (pintype "output"))
      (node (ref "TFT") (pin "4") (pinfunction "4_4") (pintype "passive"))
    )
    (net (code "48") (name "Net-(IC7D-O)") (class "Default")
      (node (ref "IC7") (pin "10") (pinfunction "O_10") (pintype "output"))
      (node (ref "TFT") (pin "5") (pinfunction "5_5") (pintype "passive"))
    )
    (net (code "49") (name "Net-(IC7E-O)") (class "Default")
      (node (ref "IC7") (pin "12") (pinfunction "O_12") (pintype "output"))
      (node (ref "TFT") (pin "3") (pinfunction "3_3") (pintype "passive"))
    )
    (net (code "50") (name "Net-(IC7F-O)") (class "Default")
      (node (ref "IC7") (pin "15") (pinfunction "O_15") (pintype "output"))
      (node (ref "TFT") (pin "2") (pinfunction "2_2") (pintype "passive"))
    )
    (net (code "51") (name "Net-(IC8A-O)") (class "Default")
      (node (ref "ETH1") (pin "MOSI") (pinfunction "MOSI_MOSI") (pintype "input"))
      (node (ref "IC8") (pin "2") (pinfunction "O_2") (pintype "output"))
    )
    (net (code "52") (name "Net-(L-IN-PadMP)") (class "Default")
      (node (ref "L-IN") (pin "MP") (pinfunction "MP_MP") (pintype "passive"))
      (node (ref "R13") (pin "1") (pinfunction "1_1") (pintype "passive"))
      (node (ref "R7") (pin "1") (pinfunction "1_1") (pintype "passive"))
      (node (ref "R8") (pin "1") (pinfunction "1_1") (pintype "passive"))
    )
    (net (code "53") (name "Net-(R-IN-PadMP)") (class "Default")
      (node (ref "R-IN") (pin "MP") (pinfunction "MP_MP") (pintype "passive"))
      (node (ref "R14") (pin "1") (pinfunction "1_1") (pintype "passive"))
      (node (ref "R5") (pin "1") (pinfunction "1_1") (pintype "passive"))
      (node (ref "R6") (pin "1") (pinfunction "1_1") (pintype "passive"))
    )
    (net (code "54") (name "Net-(R4-Pad1)") (class "Default")
      (node (ref "R4") (pin "1") (pinfunction "1_1") (pintype "passive"))
      (node (ref "TFT") (pin "6") (pinfunction "6_6") (pintype "passive"))
    )
    (net (code "55") (name "unconnected-(ETH1-PadINT)") (class "Default")
      (node (ref "ETH1") (pin "INT") (pinfunction "INT_INT") (pintype "output"))
    )
    (net (code "56") (name "unconnected-(IC1-PadCLK)") (class "Default")
      (node (ref "IC1") (pin "CLK") (pinfunction "CLK_CLK") (pintype "bidirectional"))
    )
    (net (code "57") (name "unconnected-(IC1-PadCMD)") (class "Default")
      (node (ref "IC1") (pin "CMD") (pinfunction "CMD_CMD") (pintype "bidirectional"))
    )
    (net (code "58") (name "unconnected-(IC1-PadIO0)") (class "Default")
      (node (ref "IC1") (pin "IO0") (pinfunction "IO0_IO0") (pintype "bidirectional"))
    )
    (net (code "59") (name "unconnected-(IC1-PadIO12)") (class "Default")
      (node (ref "IC1") (pin "IO12") (pinfunction "IO12_IO12") (pintype "bidirectional"))
    )
    (net (code "60") (name "unconnected-(IC1-PadIO13)") (class "Default")
      (node (ref "IC1") (pin "IO13") (pinfunction "IO13_IO13") (pintype "bidirectional"))
    )
    (net (code "61") (name "unconnected-(IC1-PadIO21)") (class "Default")
      (node (ref "IC1") (pin "IO21") (pinfunction "IO21_IO21") (pintype "bidirectional"))
    )
    (net (code "62") (name "unconnected-(IC1-PadIO34)") (class "Default")
      (node (ref "IC1") (pin "IO34") (pinfunction "IO34_IO34") (pintype "bidirectional"))
    )
    (net (code "63") (name "unconnected-(IC1-PadRX0)") (class "Default")
      (node (ref "IC1") (pin "RX0") (pinfunction "RX0_RX0") (pintype "input"))
    )
    (net (code "64") (name "unconnected-(IC1-PadSD0)") (class "Default")
      (node (ref "IC1") (pin "SD0") (pinfunction "SD0_SD0") (pintype "bidirectional"))
    )
    (net (code "65") (name "unconnected-(IC1-PadSD1)") (class "Default")
      (node (ref "IC1") (pin "SD1") (pinfunction "SD1_SD1") (pintype "bidirectional"))
    )
    (net (code "66") (name "unconnected-(IC1-PadSD2)") (class "Default")
      (node (ref "IC1") (pin "SD2") (pinfunction "SD2_SD2") (pintype "bidirectional"))
    )
    (net (code "67") (name "unconnected-(IC1-PadSD3)") (class "Default")
      (node (ref "IC1") (pin "SD3") (pinfunction "SD3_SD3") (pintype "bidirectional"))
    )
    (net (code "68") (name "unconnected-(IC1-PadVN)") (class "Default")
      (node (ref "IC1") (pin "VN") (pinfunction "VN_VN") (pintype "bidirectional"))
    )
    (net (code "69") (name "unconnected-(IC1-PadVP)") (class "Default")
      (node (ref "IC1") (pin "VP") (pinfunction "VP_VP") (pintype "bidirectional"))
    )
    (net (code "70") (name "unconnected-(IC2A-O-Pad2)") (class "Default")
      (node (ref "IC2") (pin "2") (pinfunction "O_2") (pintype "output"))
    )
    (net (code "71") (name "unconnected-(IC2C-O-Pad6)") (class "Default")
      (node (ref "IC2") (pin "6") (pinfunction "O_6") (pintype "output"))
    )
    (net (code "72") (name "unconnected-(IC2F-O-Pad15)") (class "Default")
      (node (ref "IC2") (pin "15") (pinfunction "O_15") (pintype "output"))
    )
    (net (code "73") (name "unconnected-(IC3A-O-Pad3)") (class "Default")
      (node (ref "IC3") (pin "3") (pinfunction "O_3") (pintype "tri_state"))
    )
    (net (code "74") (name "unconnected-(IC3B-O-Pad6)") (class "Default")
      (node (ref "IC3") (pin "6") (pinfunction "O_6") (pintype "tri_state"))
    )
    (net (code "75") (name "unconnected-(IC3C-O-Pad8)") (class "Default")
      (node (ref "IC3") (pin "8") (pinfunction "O_8") (pintype "tri_state"))
    )
    (net (code "76") (name "unconnected-(IC4-PadSDCS)") (class "Default")
      (node (ref "IC4") (pin "SDCS") (pinfunction "SDCS_SDCS") (pintype "input"))
    )
    (net (code "77") (name "unconnected-(IC7B-O-Pad4)") (class "Default")
      (node (ref "IC7") (pin "4") (pinfunction "O_4") (pintype "output"))
    )
    (net (code "78") (name "unconnected-(IC8B-O-Pad4)") (class "Default")
      (node (ref "IC8") (pin "4") (pinfunction "O_4") (pintype "output"))
    )
    (net (code "79") (name "unconnected-(IC8D-O-Pad10)") (class "Default")
      (node (ref "IC8") (pin "10") (pinfunction "O_10") (pintype "output"))
    )
    (net (code "80") (name "unconnected-(IC8E-O-Pad12)") (class "Default")
      (node (ref "IC8") (pin "12") (pinfunction "O_12") (pintype "output"))
    )
    (net (code "81") (name "unconnected-(IC8F-O-Pad15)") (class "Default")
      (node (ref "IC8") (pin "15") (pinfunction "O_15") (pintype "output"))
    )
  )
)
